# DIN-rail_AC-DC_24V.net
KiCad netlist of a schematic drawn in Altium Designer
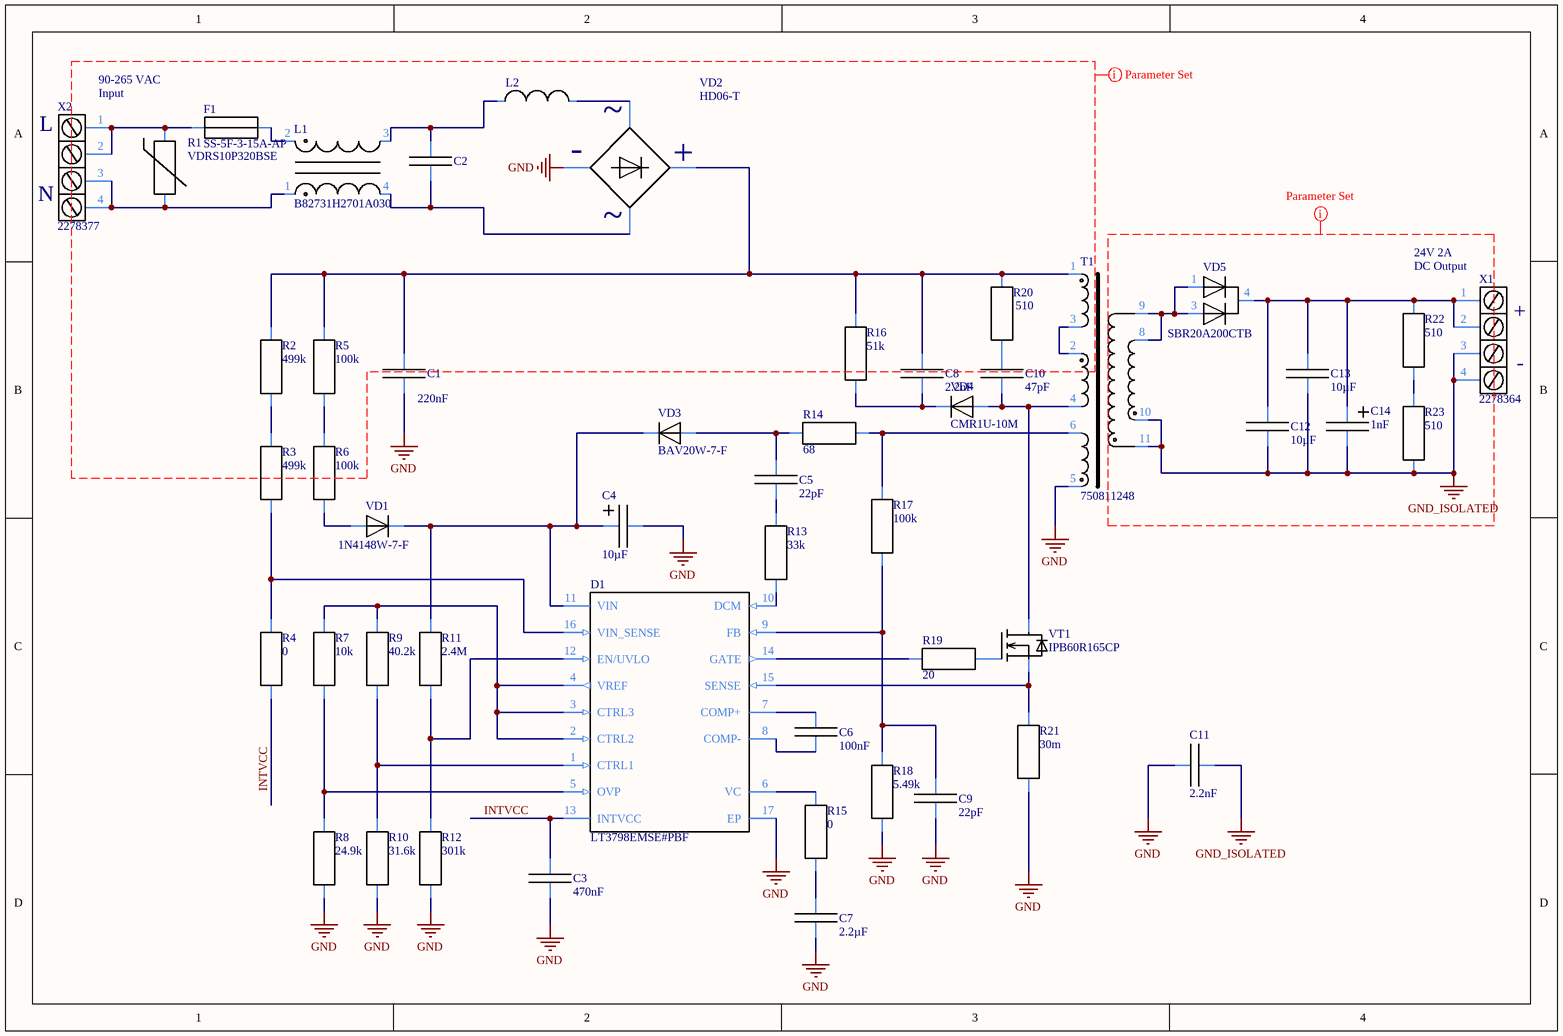
[diagram p0: DIN-rail AC-DC 24V.SchDoc]

(export (version "E")
  (design (tool "Eeschema 10.0.6"))
  (components
    (comp (ref "C1")
      (value "ECQE4224KF")
      (footprint "ECQE4224XF")
      (description "Film Capacitor, Polyester, 400V, 10% +Tol, 10% -Tol, 0.22uF, Through Hole Mount")
      (fields
        (field (name "CAPACITANCE") "220nF")
        (field (name "TOLERANCE") "10%")
        (field (name "VOLTAGE") "400V")
      )
      (libsource (lib "Anton") (part "capacitor"))
    )
    (comp (ref "C2")
      (value "ECQUAAF104M")
      (footprint "ECUAAF104")
      (description "Film Capacitor, Polypropylene, 20% +Tol, 20% -Tol, 0.1uF, Through Hole Mount")
      (fields (field (name "TOLERANCE") "20%") (field (name "VOLTAGE") "275V"))
      (libsource (lib "Anton") (part "capacitor"))
    )
    (comp (ref "C3")
      (value "0805YD475MAT2A")
      (footprint "C0805")
      (fields
        (field (name "TOLERANCE") "20%")
        (field (name "VOLTAGE") "16V")
        (field (name "CAPACITANCE") "470nF")
      )
      (libsource (lib "Anton") (part "capacitor"))
    )
    (comp (ref "C4")
      (value "50YXJ10M5X11")
      (footprint "CAPPRD200W60D500H1100")
      (fields
        (field (name "VOLTAGE") "50V")
        (field (name "CAPACITANCE") "10µF")
        (field (name "TOLERANCE") "20%")
      )
      (libsource (lib "Anton") (part "capacitor_polar"))
    )
    (comp (ref "C5")
      (value "08055A220CAT2A")
      (footprint "C0805")
      (fields (field (name "VOLTAGE") "50V") (field (name "CAPACITANCE") "22pF"))
      (libsource (lib "Anton") (part "capacitor"))
    )
    (comp (ref "C6")
      (value "C2012X7R1H104K")
      (footprint "C0805")
      (fields
        (field (name "VOLTAGE") "50V")
        (field (name "CAPACITANCE") "100nF")
        (field (name "TOLERANCE") "10%")
      )
      (libsource (lib "Anton") (part "capacitor"))
    )
    (comp (ref "C7")
      (value "C2012X5R1H225K")
      (footprint "C0805")
      (description "Cap Ceramic 2.2uF 50V X5R 10% SMD 0805 85C T/R")
      (fields
        (field (name "VOLTAGE") "50V")
        (field (name "TOLERANCE") "10%")
        (field (name "CAPACITANCE") "2.2µF")
      )
      (libsource (lib "Anton") (part "capacitor"))
    )
    (comp (ref "C8")
      (value "GRM32A7U2J222JW31D")
      (footprint "C1210")
      (fields
        (field (name "VOLTAGE") "630V")
        (field (name "TOLERANCE") "5%")
        (field (name "CAPACITANCE") "2.2nF")
      )
      (libsource (lib "Anton") (part "capacitor"))
    )
    (comp (ref "C9")
      (value "08055A220CAT2A")
      (footprint "C0805")
      (fields (field (name "VOLTAGE") "50V") (field (name "CAPACITANCE") "22pF"))
      (libsource (lib "Anton") (part "capacitor"))
    )
    (comp (ref "C10")
      (value "1206CA470KAT1A")
      (footprint "C1206")
      (fields
        (field (name "TOLERANCE") "10%")
        (field (name "VOLTAGE") "630V")
        (field (name "CAPACITANCE") "47pF")
      )
      (libsource (lib "Anton") (part "capacitor"))
    )
    (comp (ref "C11")
      (value "440LD22-R")
      (footprint "40LD22")
      (description "Ceramic Capacitor, Ceramic, 20% +Tol, 20% -Tol, Y5U, -56/+22% TC, 0.0022uF, Through Hole Mount")
      (fields
        (field (name "CAPACITANCE") "2.2nF")
        (field (name "VOLTAGE") "760V")
        (field (name "TOLERANCE") "20%")
      )
      (libsource (lib "Anton") (part "capacitor"))
    )
    (comp (ref "C12")
      (value "GRM32ER7YA106KA12L")
      (footprint "C1210")
      (fields
        (field (name "VOLTAGE") "35V")
        (field (name "TOLERANCE") "20%")
        (field (name "CAPACITANCE") "10µF")
      )
      (libsource (lib "Anton") (part "capacitor"))
    )
    (comp (ref "C13")
      (value "GRM32ER7YA106KA12L")
      (footprint "C1210")
      (fields
        (field (name "VOLTAGE") "35V")
        (field (name "TOLERANCE") "20%")
        (field (name "CAPACITANCE") "10µF")
      )
      (libsource (lib "Anton") (part "capacitor"))
    )
    (comp (ref "C14")
      (value "ELXY350ETD102MK30S")
      (footprint "CAPPRD500W60D1250H3000_1")
      (fields
        (field (name "VOLTAGE") "35V")
        (field (name "TOLERANCE") "20%")
        (field (name "CAPACITANCE") "1nF")
      )
      (libsource (lib "Anton") (part "capacitor_polar"))
    )
    (comp (ref "D1")
      (value "LT3798EMSE#PBF")
      (footprint "SOP17P50_403X490X110L53X22T284X165")
      (description "Power Factor Controller, Current-mode, 150kHz Switching Freq-Max, BIPolar, PDSO16")
      (libsource (lib "Anton") (part "LT3798"))
    )
    (comp (ref "F1")
      (value "SS-5F-3-15A-AP")
      (footprint "SS-5F")
      (description "Electric Fuse")
      (libsource (lib "Anton") (part "fuse"))
    )
    (comp (ref "L1")
      (value "B82731H2701A030")
      (footprint "B82731H")
      (description "General Purpose Inductor, 27000uH, 50%, 2 Element, Ferrite-Core")
      (fields (field (name "VOLTAGE") "250V"))
      (libsource (lib "Anton") (part "comm mode B82731M/H"))
    )
    (comp (ref "L2")
      (value "TSL1315RA-102JR78-PF")
      (footprint "TSL1315")
      (description "General Purpose Inductor, 1000uH, 5%, 1 Element")
      (fields (field (name "TOLERANCE") "5%"))
      (libsource (lib "Anton") (part "inductor"))
    )
    (comp (ref "R1")
      (value "VDRS10P320BSE")
      (footprint "VDRS10P320")
      (description "Varistor, 420V, 77J, Through Hole Mount")
      (fields (field (name "VOLTAGE") "510V"))
      (libsource (lib "Anton") (part "varistor"))
    )
    (comp (ref "R2")
      (value "CRCW1206499KFKEA")
      (footprint "R1206")
      (fields
        (field (name "POWER") "250mW")
        (field (name "TOLERANCE") "1%")
        (field (name "RESISTANCE") "499k")
      )
      (libsource (lib "Anton") (part "resistor"))
    )
    (comp (ref "R3")
      (value "CRCW1206499KFKEA")
      (footprint "R1206")
      (fields
        (field (name "POWER") "250mW")
        (field (name "TOLERANCE") "1%")
        (field (name "RESISTANCE") "499k")
      )
      (libsource (lib "Anton") (part "resistor"))
    )
    (comp (ref "R4")
      (value "CRCW08050000Z0EA")
      (footprint "R0805")
      (description "Fixed Resistor, Metal Glaze/thick Film, 0.125W, 0ohm, Surface Mount, 0805")
      (fields (field (name "POWER") "125mW") (field (name "TOLERANCE") "0%") (field (name "RESISTANCE") "0"))
      (libsource (lib "Anton") (part "resistor"))
    )
    (comp (ref "R5")
      (value "CRCW1206100KFKEA")
      (footprint "R1206")
      (fields
        (field (name "RESISTANCE") "100k")
        (field (name "TOLERANCE") "1%")
        (field (name "POWER") "250mW")
      )
      (libsource (lib "Anton") (part "resistor"))
    )
    (comp (ref "R6")
      (value "CRCW1206100KFKEA")
      (footprint "R1206")
      (fields
        (field (name "RESISTANCE") "100k")
        (field (name "TOLERANCE") "1%")
        (field (name "POWER") "250mW")
      )
      (libsource (lib "Anton") (part "resistor"))
    )
    (comp (ref "R7")
      (value "CRCW080510K0FKEA")
      (footprint "R0805")
      (fields
        (field (name "POWER") "125mW")
        (field (name "RESISTANCE") "10k")
        (field (name "TOLERANCE") "1%")
      )
      (libsource (lib "") (part "resistor_1"))
    )
    (comp (ref "R8")
      (value "CRCW080524K9FKEA")
      (footprint "R0805")
      (fields
        (field (name "POWER") "125mW")
        (field (name "TOLERANCE") "1%")
        (field (name "RESISTANCE") "24.9k")
      )
      (libsource (lib "") (part "resistor_1"))
    )
    (comp (ref "R9")
      (value "CRCW080540K2FKEA")
      (footprint "R0805")
      (fields
        (field (name "TOLERANCE") "1%")
        (field (name "POWER") "125mW")
        (field (name "RESISTANCE") "40.2k")
      )
      (libsource (lib "") (part "resistor_1"))
    )
    (comp (ref "R10")
      (value "CRCW080531K6FKEA")
      (footprint "R0805")
      (fields
        (field (name "POWER") "125mW")
        (field (name "RESISTANCE") "31.6k")
        (field (name "TOLERANCE") "1%")
      )
      (libsource (lib "") (part "resistor_1"))
    )
    (comp (ref "R11")
      (value "CRCW08052M40JNEA")
      (footprint "R0805")
      (fields
        (field (name "TOLERANCE") "5%")
        (field (name "RESISTANCE") "2.4M")
        (field (name "POWER") "125mW")
      )
      (libsource (lib "") (part "resistor_1"))
    )
    (comp (ref "R12")
      (value "CRCW0805301KFKEA")
      (footprint "R0805")
      (fields
        (field (name "TOLERANCE") "1%")
        (field (name "RESISTANCE") "301k")
        (field (name "POWER") "125mW")
      )
      (libsource (lib "") (part "resistor_1"))
    )
    (comp (ref "R13")
      (value "CRCW080533K0JNEA")
      (footprint "R0805")
      (fields
        (field (name "TOLERANCE") "5%")
        (field (name "POWER") "125mW")
        (field (name "RESISTANCE") "33k")
      )
      (libsource (lib "") (part "resistor_1"))
    )
    (comp (ref "R14")
      (value "CRCW080568R0FKEA")
      (footprint "R0805")
      (fields (field (name "TOLERANCE") "1%") (field (name "RESISTANCE") "68") (field (name "POWER") "125mW"))
      (libsource (lib "") (part "resistor_2"))
    )
    (comp (ref "R15")
      (value "CRCW08050000Z0EA")
      (footprint "R0805")
      (description "Fixed Resistor, Metal Glaze/thick Film, 0.125W, 0ohm, Surface Mount, 0805")
      (fields (field (name "POWER") "125mW") (field (name "TOLERANCE") "0%") (field (name "RESISTANCE") "0"))
      (libsource (lib "") (part "resistor_1"))
    )
    (comp (ref "R16")
      (value "CRCW121051K0JNEA")
      (footprint "R1210")
      (fields
        (field (name "RESISTANCE") "51k")
        (field (name "TOLERANCE") "5%")
        (field (name "POWER") "500mW")
      )
      (libsource (lib "") (part "resistor_1"))
    )
    (comp (ref "R17")
      (value "CRCW0805100KFKEA")
      (footprint "R0805")
      (fields
        (field (name "TOLERANCE") "1%")
        (field (name "POWER") "125mW")
        (field (name "RESISTANCE") "100k")
      )
      (libsource (lib "Anton") (part "resistor"))
    )
    (comp (ref "R18")
      (value "CRCW08055K49FKEA")
      (footprint "R0805")
      (fields
        (field (name "TOLERANCE") "1%")
        (field (name "POWER") "125mW")
        (field (name "RESISTANCE") "5.49k")
      )
      (libsource (lib "Anton") (part "resistor"))
    )
    (comp (ref "R19")
      (value "CRCW080520R0FKEA")
      (footprint "R0805")
      (fields (field (name "RESISTANCE") "20") (field (name "POWER") "125mW") (field (name "TOLERANCE") "1%"))
      (libsource (lib "") (part "resistor_2"))
    )
    (comp (ref "R20")
      (value "CRCW1210510RJNEA")
      (footprint "R1210")
      (fields
        (field (name "TOLERANCE") "5%")
        (field (name "RESISTANCE") "510")
        (field (name "POWER") "500mW")
      )
      (libsource (lib "") (part "resistor_1"))
    )
    (comp (ref "R21")
      (value "WSL1206R0300FEA")
      (footprint "R1206")
      (description "Fixed Resistor, Metal Strip, 0.25W, 0.03ohm, 0.0866V, 1% +/-Tol, 75ppm/Cel, Surface Mount, 1206")
      (fields
        (field (name "RESISTANCE") "30m")
        (field (name "POWER") "250mW")
        (field (name "TOLERANCE") "1%")
      )
      (libsource (lib "") (part "resistor_1"))
    )
    (comp (ref "R22")
      (value "CRCW1210510RJNEA")
      (footprint "R1210")
      (fields
        (field (name "TOLERANCE") "5%")
        (field (name "RESISTANCE") "510")
        (field (name "POWER") "500mW")
      )
      (libsource (lib "") (part "resistor_1"))
    )
    (comp (ref "R23")
      (value "CRCW1210510RJNEA")
      (footprint "R1210")
      (fields
        (field (name "TOLERANCE") "5%")
        (field (name "RESISTANCE") "510")
        (field (name "POWER") "500mW")
      )
      (libsource (lib "") (part "resistor_1"))
    )
    (comp (ref "T1")
      (value "750811248")
      (footprint "750811248")
      (description "Datacom Transformer")
      (libsource (lib "Anton") (part "wurth_750811248"))
    )
    (comp (ref "VD1")
      (value "1N4148W-7-F")
      (footprint "SOD-123")
      (description "Rectifier Diode, 1 Phase, 1 Element, 0.15A, 100V V(RRM), Silicon")
      (libsource (lib "Anton") (part "diode"))
    )
    (comp (ref "VD2")
      (value "HD06-T")
      (footprint "SOIC250P600X300-4L")
      (description "Bridge Rectifier Diode, 1 Phase, 0.8A, 600V V(RRM), Silicon")
      (libsource (lib "Anton") (part "HD0X"))
    )
    (comp (ref "VD3")
      (value "BAV20W-7-F")
      (footprint "SOD-123")
      (description "Rectifier Diode, 1 Phase, 1 Element, 0.4A, 150V V(RRM), Silicon")
      (libsource (lib "Anton") (part "diode"))
    )
    (comp (ref "VD4")
      (value "CMR1U-10M")
      (footprint "SMA")
      (description "Rectifier Diode, 1 Phase, 1 Element, 1A, 1000V V(RRM)")
      (libsource (lib "Anton") (part "diode"))
    )
    (comp (ref "VD5")
      (value "SBR20A200CTB")
      (footprint "D2PAK")
      (description "Rectifier Diode, 1 Phase, 2 Element, 20A, 200V V(RRM), Silicon, TO-263AB")
      (libsource (lib "Anton") (part "diodes_comm_cat_d2pak"))
    )
    (comp (ref "VT1")
      (value "IPB60R165CP")
      (footprint "D2PAK")
      (fields (field (name "POWER") "192W"))
      (libsource (lib "Anton") (part "mosfet n-ch enh mode D2PAK"))
    )
    (comp (ref "X1")
      (value "2278364")
      (footprint "MCO 1,5_4-G1L-3,5 KMGY")
      (description "Barrier Strip Terminal Block")
      (fields (field (name "VOLTAGE") "320V"))
      (libsource (lib "") (part "terminal_block_4p_1"))
    )
    (comp (ref "X2")
      (value "2278377")
      (footprint "MCO 1,5_4-G1R-3,5 KMGY")
      (description "Strip Terminal Block, 8A, 1 Row(s), 1 Deck(s)")
      (fields (field (name "VOLTAGE") "320V"))
      (libsource (lib "Anton") (part "terminal_block_4p"))
    )
  )
  (nets
    (net (code "1") (name "/INTVCC") (class "Default")
      (node (ref "C3") (pin "2") (pinfunction "2_2") (pintype "passive"))
      (node (ref "D1") (pin "13") (pinfunction "INTVCC_13") (pintype "power_in"))
      (node (ref "R4") (pin "2") (pinfunction "2_2") (pintype "passive"))
    )
    (net (code "2") (name "GND") (class "Default")
      (node (ref "C1") (pin "2") (pinfunction "2_2") (pintype "passive"))
      (node (ref "C11") (pin "1") (pinfunction "1_1") (pintype "passive"))
      (node (ref "C3") (pin "1") (pinfunction "1_1") (pintype "passive"))
      (node (ref "C4") (pin "2") (pinfunction "2_2") (pintype "passive"))
      (node (ref "C7") (pin "1") (pinfunction "1_1") (pintype "passive"))
      (node (ref "C9") (pin "2") (pinfunction "2_2") (pintype "passive"))
      (node (ref "D1") (pin "17") (pinfunction "EP_17") (pintype "power_in"))
      (node (ref "R10") (pin "1") (pinfunction "1_1") (pintype "passive"))
      (node (ref "R12") (pin "1") (pinfunction "1_1") (pintype "passive"))
      (node (ref "R18") (pin "2") (pinfunction "2_2") (pintype "passive"))
      (node (ref "R21") (pin "1") (pinfunction "1_1") (pintype "passive"))
      (node (ref "R8") (pin "1") (pinfunction "1_1") (pintype "passive"))
      (node (ref "T1") (pin "5") (pinfunction "5_5") (pintype "passive"))
      (node (ref "VD2") (pin "2") (pinfunction "2_2") (pintype "passive"))
    )
    (net (code "3") (name "GND_ISOLATED") (class "Default")
      (node (ref "C11") (pin "2") (pinfunction "2_2") (pintype "passive"))
      (node (ref "C12") (pin "1") (pinfunction "1_1") (pintype "passive"))
      (node (ref "C13") (pin "1") (pinfunction "1_1") (pintype "passive"))
      (node (ref "C14") (pin "2") (pinfunction "2_2") (pintype "passive"))
      (node (ref "R23") (pin "1") (pinfunction "1_1") (pintype "passive"))
      (node (ref "T1") (pin "10") (pinfunction "10_10") (pintype "passive"))
      (node (ref "T1") (pin "11") (pinfunction "11_11") (pintype "passive"))
      (node (ref "X1") (pin "3") (pinfunction "3_3") (pintype "passive"))
      (node (ref "X1") (pin "4") (pinfunction "4_4") (pintype "passive"))
    )
    (net (code "4") (name "Net-(C1-Pad1)") (class "Default")
      (node (ref "C1") (pin "1") (pinfunction "1_1") (pintype "passive"))
      (node (ref "C8") (pin "2") (pinfunction "2_2") (pintype "passive"))
      (node (ref "R16") (pin "2") (pinfunction "2_2") (pintype "passive"))
      (node (ref "R2") (pin "1") (pinfunction "1_1") (pintype "passive"))
      (node (ref "R20") (pin "2") (pinfunction "2_2") (pintype "passive"))
      (node (ref "R5") (pin "1") (pinfunction "1_1") (pintype "passive"))
      (node (ref "T1") (pin "1") (pinfunction "1_1") (pintype "passive"))
      (node (ref "VD2") (pin "1") (pinfunction "1_1") (pintype "passive"))
    )
    (net (code "5") (name "Net-(C2-Pad1)") (class "Default")
      (node (ref "C2") (pin "1") (pinfunction "1_1") (pintype "passive"))
      (node (ref "L1") (pin "4") (pinfunction "4_4") (pintype "passive"))
      (node (ref "VD2") (pin "4") (pinfunction "4_4") (pintype "passive"))
    )
    (net (code "6") (name "Net-(C2-Pad2)") (class "Default")
      (node (ref "C2") (pin "2") (pinfunction "2_2") (pintype "passive"))
      (node (ref "L1") (pin "3") (pinfunction "3_3") (pintype "passive"))
      (node (ref "L2") (pin "1") (pinfunction "1_1") (pintype "passive"))
    )
    (net (code "7") (name "Net-(C5-Pad1)") (class "Default")
      (node (ref "C5") (pin "1") (pinfunction "1_1") (pintype "passive"))
      (node (ref "R13") (pin "2") (pinfunction "2_2") (pintype "passive"))
    )
    (net (code "8") (name "Net-(C5-Pad2)") (class "Default")
      (node (ref "C5") (pin "2") (pinfunction "2_2") (pintype "passive"))
      (node (ref "R14") (pin "1") (pinfunction "1_1") (pintype "passive"))
      (node (ref "VD3") (pin "1") (pinfunction "1_1") (pintype "passive"))
    )
    (net (code "9") (name "Net-(C7-Pad2)") (class "Default")
      (node (ref "C7") (pin "2") (pinfunction "2_2") (pintype "passive"))
      (node (ref "R15") (pin "1") (pinfunction "1_1") (pintype "passive"))
    )
    (net (code "10") (name "Net-(C8-Pad1)") (class "Default")
      (node (ref "C8") (pin "1") (pinfunction "1_1") (pintype "passive"))
      (node (ref "R16") (pin "1") (pinfunction "1_1") (pintype "passive"))
      (node (ref "VD4") (pin "2") (pinfunction "2_2") (pintype "passive"))
    )
    (net (code "11") (name "Net-(C10-Pad1)") (class "Default")
      (node (ref "C10") (pin "1") (pinfunction "1_1") (pintype "passive"))
      (node (ref "T1") (pin "4") (pinfunction "4_4") (pintype "passive"))
      (node (ref "VD4") (pin "1") (pinfunction "1_1") (pintype "passive"))
      (node (ref "VT1") (pin "4") (pinfunction "4_4") (pintype "passive"))
    )
    (net (code "12") (name "Net-(C10-Pad2)") (class "Default")
      (node (ref "C10") (pin "2") (pinfunction "2_2") (pintype "passive"))
      (node (ref "R20") (pin "1") (pinfunction "1_1") (pintype "passive"))
    )
    (net (code "13") (name "Net-(C12-Pad2)") (class "Default")
      (node (ref "C12") (pin "2") (pinfunction "2_2") (pintype "passive"))
      (node (ref "C13") (pin "2") (pinfunction "2_2") (pintype "passive"))
      (node (ref "C14") (pin "1") (pinfunction "1_1") (pintype "passive"))
      (node (ref "R22") (pin "2") (pinfunction "2_2") (pintype "passive"))
      (node (ref "VD5") (pin "4") (pinfunction "4_4") (pintype "passive"))
      (node (ref "X1") (pin "1") (pinfunction "1_1") (pintype "passive"))
      (node (ref "X1") (pin "2") (pinfunction "2_2") (pintype "passive"))
    )
    (net (code "14") (name "Net-(D1-COMP+)") (class "Default")
      (node (ref "C6") (pin "1") (pinfunction "1_1") (pintype "passive"))
      (node (ref "D1") (pin "7") (pinfunction "COMP+_7") (pintype "passive"))
    )
    (net (code "15") (name "Net-(D1-COMP-)") (class "Default")
      (node (ref "C6") (pin "2") (pinfunction "2_2") (pintype "passive"))
      (node (ref "D1") (pin "8") (pinfunction "COMP-_8") (pintype "passive"))
    )
    (net (code "16") (name "Net-(D1-CTRL1)") (class "Default")
      (node (ref "D1") (pin "1") (pinfunction "CTRL1_1") (pintype "input"))
      (node (ref "R10") (pin "2") (pinfunction "2_2") (pintype "passive"))
      (node (ref "R9") (pin "1") (pinfunction "1_1") (pintype "passive"))
    )
    (net (code "17") (name "Net-(D1-CTRL2)") (class "Default")
      (node (ref "D1") (pin "2") (pinfunction "CTRL2_2") (pintype "input"))
      (node (ref "D1") (pin "3") (pinfunction "CTRL3_3") (pintype "input"))
      (node (ref "D1") (pin "4") (pinfunction "VREF_4") (pintype "output"))
      (node (ref "R7") (pin "2") (pinfunction "2_2") (pintype "passive"))
      (node (ref "R9") (pin "2") (pinfunction "2_2") (pintype "passive"))
    )
    (net (code "18") (name "Net-(D1-DCM)") (class "Default")
      (node (ref "D1") (pin "10") (pinfunction "DCM_10") (pintype "input"))
      (node (ref "R13") (pin "1") (pinfunction "1_1") (pintype "passive"))
    )
    (net (code "19") (name "Net-(D1-EN{slash}UVLO)") (class "Default")
      (node (ref "D1") (pin "12") (pinfunction "EN/UVLO_12") (pintype "input"))
      (node (ref "R11") (pin "1") (pinfunction "1_1") (pintype "passive"))
      (node (ref "R12") (pin "2") (pinfunction "2_2") (pintype "passive"))
    )
    (net (code "20") (name "Net-(D1-FB)") (class "Default")
      (node (ref "C9") (pin "1") (pinfunction "1_1") (pintype "passive"))
      (node (ref "D1") (pin "9") (pinfunction "FB_9") (pintype "input"))
      (node (ref "R17") (pin "2") (pinfunction "2_2") (pintype "passive"))
      (node (ref "R18") (pin "1") (pinfunction "1_1") (pintype "passive"))
    )
    (net (code "21") (name "Net-(D1-GATE)") (class "Default")
      (node (ref "D1") (pin "14") (pinfunction "GATE_14") (pintype "output"))
      (node (ref "R19") (pin "1") (pinfunction "1_1") (pintype "passive"))
    )
    (net (code "22") (name "Net-(D1-OVP)") (class "Default")
      (node (ref "D1") (pin "5") (pinfunction "OVP_5") (pintype "input"))
      (node (ref "R7") (pin "1") (pinfunction "1_1") (pintype "passive"))
      (node (ref "R8") (pin "2") (pinfunction "2_2") (pintype "passive"))
    )
    (net (code "23") (name "Net-(D1-SENSE)") (class "Default")
      (node (ref "D1") (pin "15") (pinfunction "SENSE_15") (pintype "input"))
      (node (ref "R21") (pin "2") (pinfunction "2_2") (pintype "passive"))
      (node (ref "VT1") (pin "3") (pinfunction "3_3") (pintype "passive"))
    )
    (net (code "24") (name "Net-(D1-VC)") (class "Default")
      (node (ref "D1") (pin "6") (pinfunction "VC_6") (pintype "passive"))
      (node (ref "R15") (pin "2") (pinfunction "2_2") (pintype "passive"))
    )
    (net (code "25") (name "Net-(D1-VIN)") (class "Default")
      (node (ref "C4") (pin "1") (pinfunction "1_1") (pintype "passive"))
      (node (ref "D1") (pin "11") (pinfunction "VIN_11") (pintype "power_in"))
      (node (ref "R11") (pin "2") (pinfunction "2_2") (pintype "passive"))
      (node (ref "VD1") (pin "2") (pinfunction "2_2") (pintype "passive"))
      (node (ref "VD3") (pin "2") (pinfunction "2_2") (pintype "passive"))
    )
    (net (code "26") (name "Net-(D1-VIN_SENSE)") (class "Default")
      (node (ref "D1") (pin "16") (pinfunction "VIN_SENSE_16") (pintype "input"))
      (node (ref "R3") (pin "2") (pinfunction "2_2") (pintype "passive"))
      (node (ref "R4") (pin "1") (pinfunction "1_1") (pintype "passive"))
    )
    (net (code "27") (name "Net-(F1-Pad1)") (class "Default")
      (node (ref "F1") (pin "1") (pinfunction "1_1") (pintype "passive"))
      (node (ref "R1") (pin "2") (pinfunction "2_2") (pintype "passive"))
      (node (ref "X2") (pin "1") (pinfunction "1_1") (pintype "passive"))
      (node (ref "X2") (pin "2") (pinfunction "2_2") (pintype "passive"))
    )
    (net (code "28") (name "Net-(F1-Pad2)") (class "Default")
      (node (ref "F1") (pin "2") (pinfunction "2_2") (pintype "passive"))
      (node (ref "L1") (pin "2") (pinfunction "2_2") (pintype "passive"))
    )
    (net (code "29") (name "Net-(L1-Pad1)") (class "Default")
      (node (ref "L1") (pin "1") (pinfunction "1_1") (pintype "passive"))
      (node (ref "R1") (pin "1") (pinfunction "1_1") (pintype "passive"))
      (node (ref "X2") (pin "3") (pinfunction "3_3") (pintype "passive"))
      (node (ref "X2") (pin "4") (pinfunction "4_4") (pintype "passive"))
    )
    (net (code "30") (name "Net-(L2-Pad2)") (class "Default")
      (node (ref "L2") (pin "2") (pinfunction "2_2") (pintype "passive"))
      (node (ref "VD2") (pin "3") (pinfunction "3_3") (pintype "passive"))
    )
    (net (code "31") (name "Net-(R2-Pad2)") (class "Default")
      (node (ref "R2") (pin "2") (pinfunction "2_2") (pintype "passive"))
      (node (ref "R3") (pin "1") (pinfunction "1_1") (pintype "passive"))
    )
    (net (code "32") (name "Net-(R5-Pad2)") (class "Default")
      (node (ref "R5") (pin "2") (pinfunction "2_2") (pintype "passive"))
      (node (ref "R6") (pin "1") (pinfunction "1_1") (pintype "passive"))
    )
    (net (code "33") (name "Net-(R6-Pad2)") (class "Default")
      (node (ref "R6") (pin "2") (pinfunction "2_2") (pintype "passive"))
      (node (ref "VD1") (pin "1") (pinfunction "1_1") (pintype "passive"))
    )
    (net (code "34") (name "Net-(R14-Pad2)") (class "Default")
      (node (ref "R14") (pin "2") (pinfunction "2_2") (pintype "passive"))
      (node (ref "R17") (pin "1") (pinfunction "1_1") (pintype "passive"))
      (node (ref "T1") (pin "6") (pinfunction "6_6") (pintype "passive"))
    )
    (net (code "35") (name "Net-(R19-Pad2)") (class "Default")
      (node (ref "R19") (pin "2") (pinfunction "2_2") (pintype "passive"))
      (node (ref "VT1") (pin "1") (pinfunction "1_1") (pintype "passive"))
    )
    (net (code "36") (name "Net-(R22-Pad1)") (class "Default")
      (node (ref "R22") (pin "1") (pinfunction "1_1") (pintype "passive"))
      (node (ref "R23") (pin "2") (pinfunction "2_2") (pintype "passive"))
    )
    (net (code "37") (name "Net-(T1-Pad2)") (class "Default")
      (node (ref "T1") (pin "2") (pinfunction "2_2") (pintype "passive"))
      (node (ref "T1") (pin "3") (pinfunction "3_3") (pintype "passive"))
    )
    (net (code "38") (name "Net-(T1-Pad8)") (class "Default")
      (node (ref "T1") (pin "8") (pinfunction "8_8") (pintype "passive"))
      (node (ref "T1") (pin "9") (pinfunction "9_9") (pintype "passive"))
      (node (ref "VD5") (pin "1") (pinfunction "1_1") (pintype "passive"))
      (node (ref "VD5") (pin "3") (pinfunction "3_3") (pintype "passive"))
    )
  )
)
